# CM4_Conn.net
KiCad netlist of a schematic drawn in Altium Designer
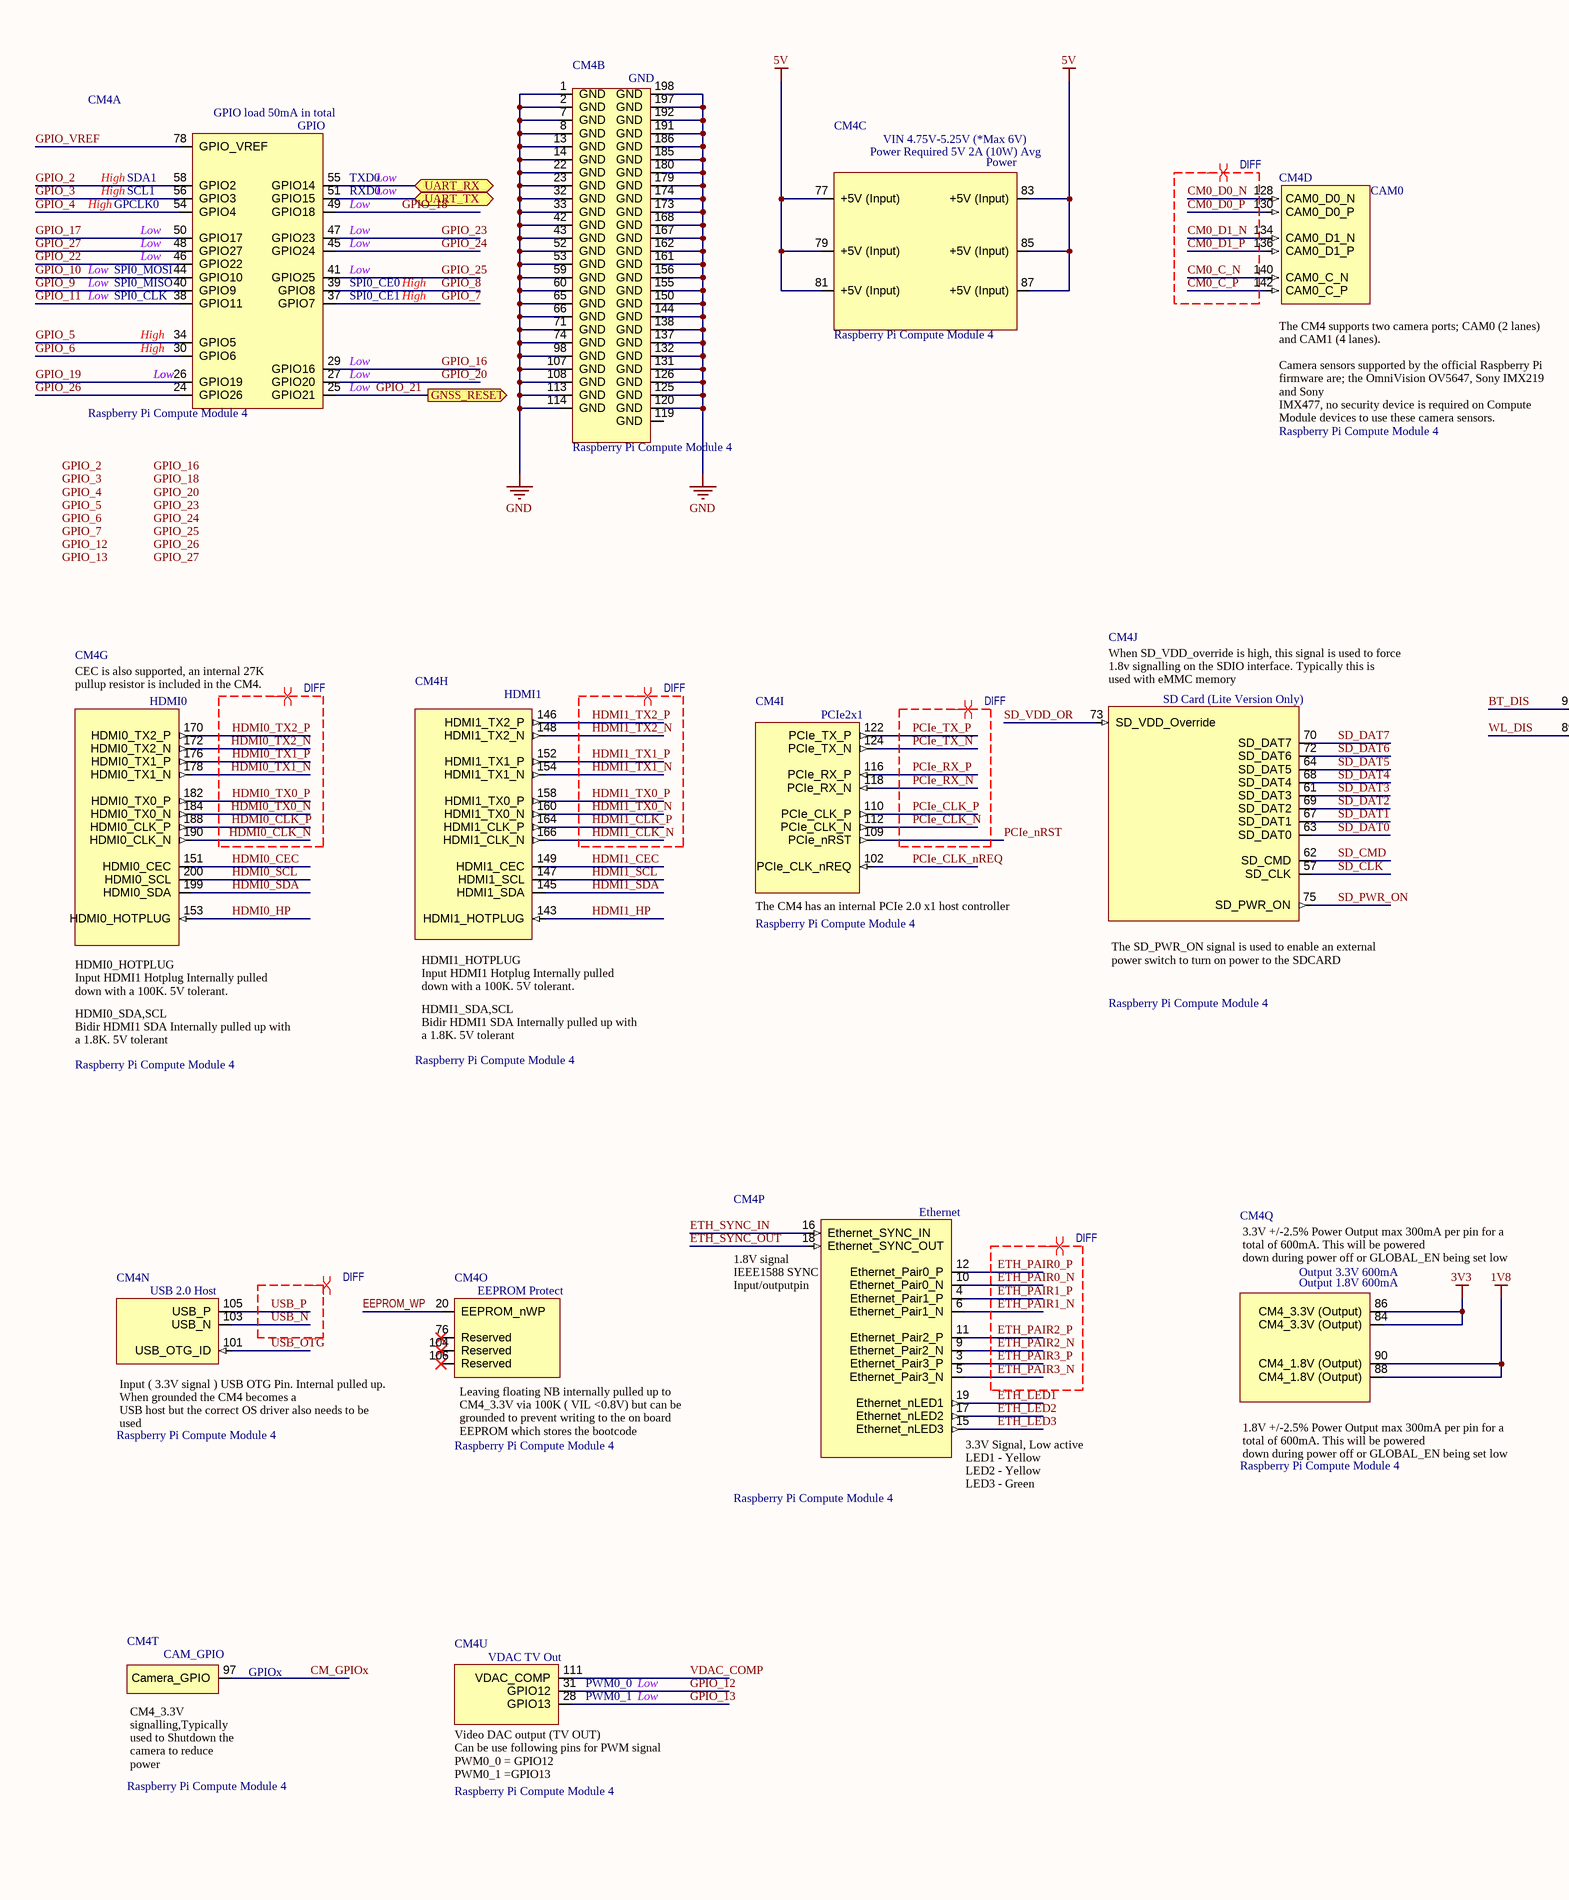
[diagram p0: CM4_Conn.SchDoc, left]
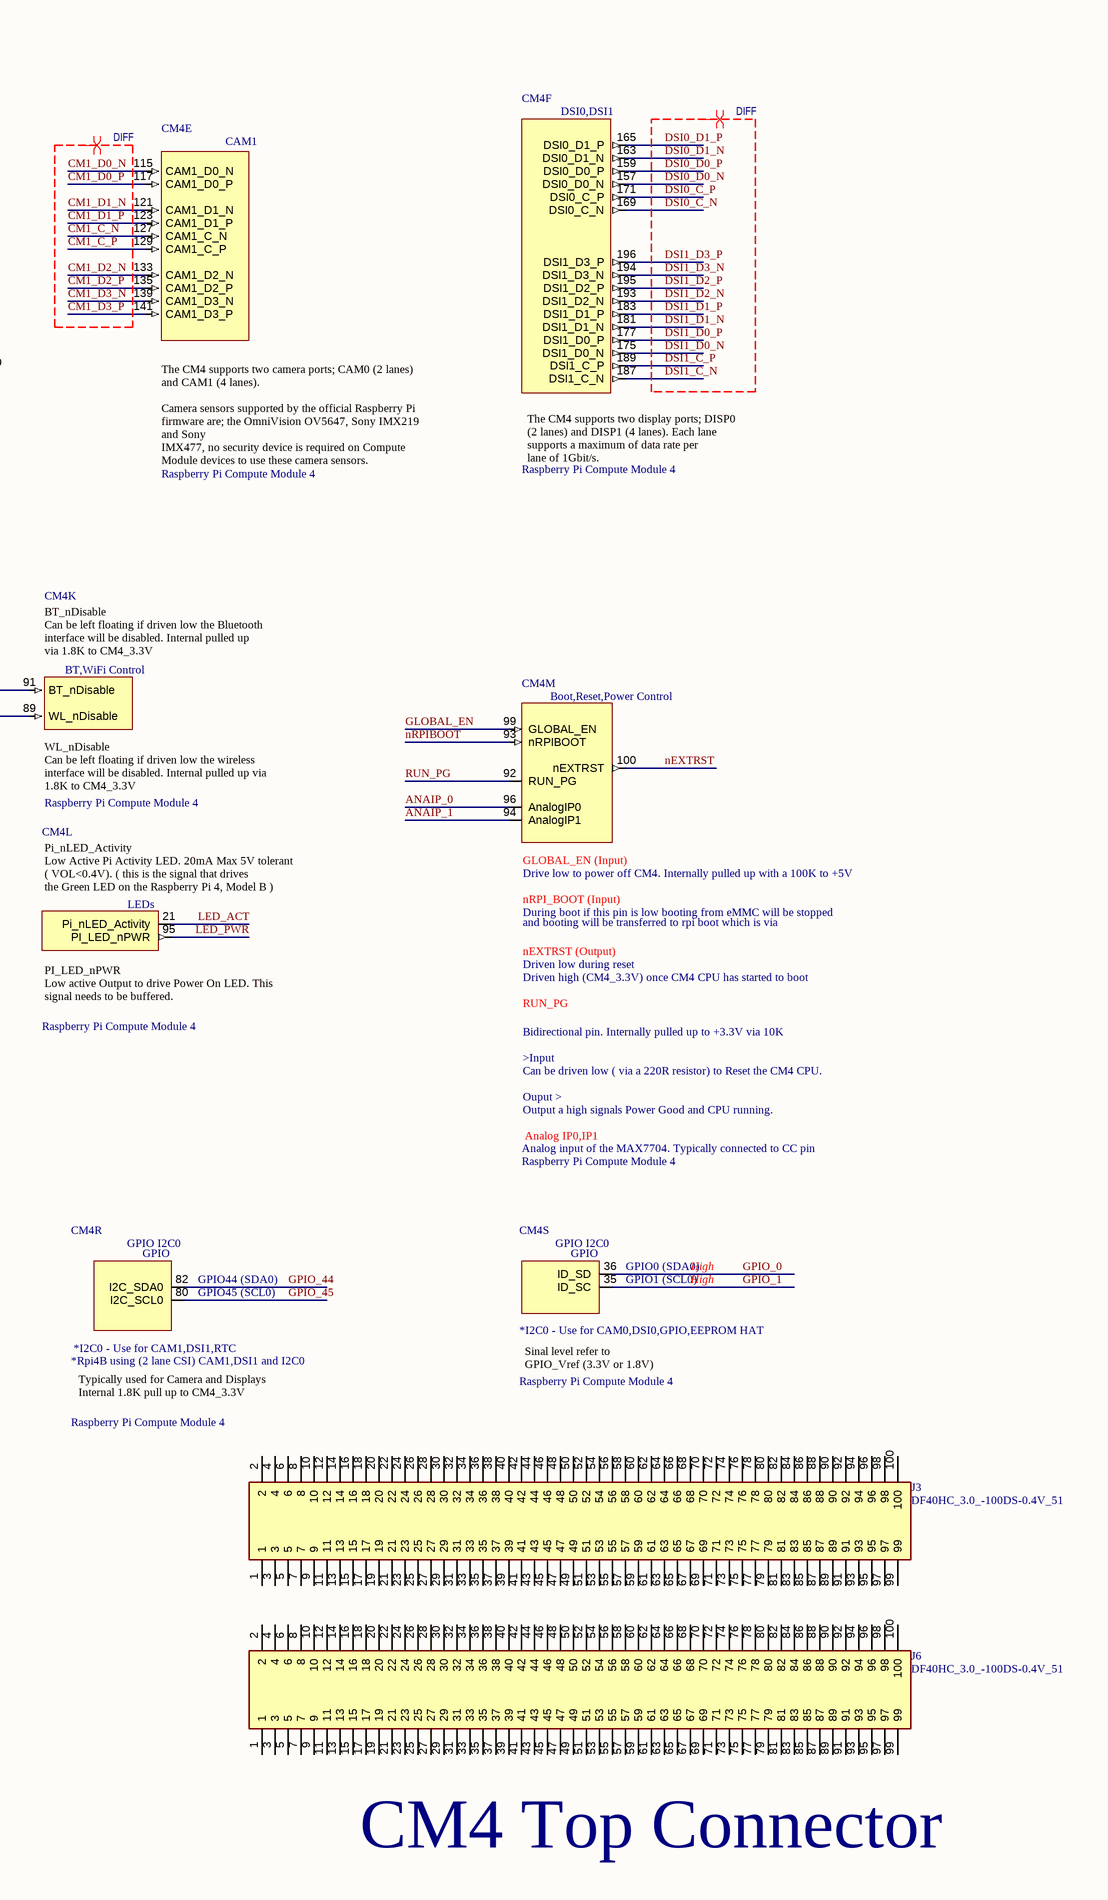
[diagram p1: CM4_Conn.SchDoc, right]

(export (version "E")
  (design (tool "Eeschema 10.0.6"))
  (components
    (comp (ref "CM4")
      (value "Raspberry Pi Compute Module 4")
      (footprint "CM4-F40C-100DS-0.4v_1.5mm_0mm")
      (description "Raspberry Pi Compute Module 4 by Amornthep Phunsin")
      (libsource (lib "CM4") (part "CM4"))
    )
    (comp (ref "J3")
      (value "DF40HC_3.0_-100DS-0.4V_51")
      (footprint "SamacSys:DF40HC30100DS04V51")
      (description "Connector")
      (fields
        (field (name "MANUFACTURER_PART_NUMBER") "DF40HC(3.0)-100DS-0.4V(51")
        (field (name "MOUSER PART NUMBER") "798-DF40HC30100DS451")
      )
      (libsource (lib "SamacSys") (part "DF40HC_3.0_-100DS-0.4V_51"))
    )
    (comp (ref "J6")
      (value "DF40HC_3.0_-100DS-0.4V_51")
      (footprint "SamacSys:DF40HC30100DS04V51")
      (description "Connector")
      (fields
        (field (name "MANUFACTURER_PART_NUMBER") "DF40HC(3.0)-100DS-0.4V(51")
        (field (name "MOUSER PART NUMBER") "798-DF40HC30100DS451")
      )
      (libsource (lib "SamacSys") (part "DF40HC_3.0_-100DS-0.4V_51"))
    )
  )
  (nets
    (net (code "1") (name "/ANAIP_0") (class "Default")
      (node (ref "CM4") (pin "96") (pinfunction "AnalogIP0_96") (pintype "passive"))
    )
    (net (code "2") (name "/ANAIP_1") (class "Default")
      (node (ref "CM4") (pin "94") (pinfunction "AnalogIP1_94") (pintype "passive"))
    )
    (net (code "3") (name "/BT_DIS") (class "Default")
      (node (ref "CM4") (pin "91") (pinfunction "BT_nDisable_91") (pintype "input"))
    )
    (net (code "4") (name "/CM0_C_N") (class "Default")
      (node (ref "CM4") (pin "140") (pinfunction "CAM0_C_N_140") (pintype "input"))
    )
    (net (code "5") (name "/CM0_C_P") (class "Default")
      (node (ref "CM4") (pin "142") (pinfunction "CAM0_C_P_142") (pintype "input"))
    )
    (net (code "6") (name "/CM0_D0_N") (class "Default")
      (node (ref "CM4") (pin "128") (pinfunction "CAM0_D0_N_128") (pintype "input"))
    )
    (net (code "7") (name "/CM0_D0_P") (class "Default")
      (node (ref "CM4") (pin "130") (pinfunction "CAM0_D0_P_130") (pintype "input"))
    )
    (net (code "8") (name "/CM0_D1_N") (class "Default")
      (node (ref "CM4") (pin "134") (pinfunction "CAM0_D1_N_134") (pintype "input"))
    )
    (net (code "9") (name "/CM0_D1_P") (class "Default")
      (node (ref "CM4") (pin "136") (pinfunction "CAM0_D1_P_136") (pintype "input"))
    )
    (net (code "10") (name "/CM1_C_N") (class "Default")
      (node (ref "CM4") (pin "127") (pinfunction "CAM1_C_N_127") (pintype "input"))
    )
    (net (code "11") (name "/CM1_C_P") (class "Default")
      (node (ref "CM4") (pin "129") (pinfunction "CAM1_C_P_129") (pintype "input"))
    )
    (net (code "12") (name "/CM1_D0_N") (class "Default")
      (node (ref "CM4") (pin "115") (pinfunction "CAM1_D0_N_115") (pintype "input"))
    )
    (net (code "13") (name "/CM1_D0_P") (class "Default")
      (node (ref "CM4") (pin "117") (pinfunction "CAM1_D0_P_117") (pintype "input"))
    )
    (net (code "14") (name "/CM1_D1_N") (class "Default")
      (node (ref "CM4") (pin "121") (pinfunction "CAM1_D1_N_121") (pintype "input"))
    )
    (net (code "15") (name "/CM1_D1_P") (class "Default")
      (node (ref "CM4") (pin "123") (pinfunction "CAM1_D1_P_123") (pintype "input"))
    )
    (net (code "16") (name "/CM1_D2_N") (class "Default")
      (node (ref "CM4") (pin "133") (pinfunction "CAM1_D2_N_133") (pintype "input"))
    )
    (net (code "17") (name "/CM1_D2_P") (class "Default")
      (node (ref "CM4") (pin "135") (pinfunction "CAM1_D2_P_135") (pintype "input"))
    )
    (net (code "18") (name "/CM1_D3_N") (class "Default")
      (node (ref "CM4") (pin "139") (pinfunction "CAM1_D3_N_139") (pintype "input"))
    )
    (net (code "19") (name "/CM1_D3_P") (class "Default")
      (node (ref "CM4") (pin "141") (pinfunction "CAM1_D3_P_141") (pintype "input"))
    )
    (net (code "20") (name "/CM_GPIOx") (class "Default")
      (node (ref "CM4") (pin "97") (pinfunction "Camera_GPIO_97") (pintype "passive"))
    )
    (net (code "21") (name "/DSI0_C_N") (class "Default")
      (node (ref "CM4") (pin "169") (pinfunction "DSI0_C_N_169") (pintype "output"))
    )
    (net (code "22") (name "/DSI0_C_P") (class "Default")
      (node (ref "CM4") (pin "171") (pinfunction "DSI0_C_P_171") (pintype "output"))
    )
    (net (code "23") (name "/DSI0_D0_N") (class "Default")
      (node (ref "CM4") (pin "157") (pinfunction "DSI0_D0_N_157") (pintype "output"))
    )
    (net (code "24") (name "/DSI0_D0_P") (class "Default")
      (node (ref "CM4") (pin "159") (pinfunction "DSI0_D0_P_159") (pintype "output"))
    )
    (net (code "25") (name "/DSI0_D1_N") (class "Default")
      (node (ref "CM4") (pin "163") (pinfunction "DSI0_D1_N_163") (pintype "output"))
    )
    (net (code "26") (name "/DSI0_D1_P") (class "Default")
      (node (ref "CM4") (pin "165") (pinfunction "DSI0_D1_P_165") (pintype "output"))
    )
    (net (code "27") (name "/DSI1_C_N") (class "Default")
      (node (ref "CM4") (pin "187") (pinfunction "DSI1_C_N_187") (pintype "output"))
    )
    (net (code "28") (name "/DSI1_C_P") (class "Default")
      (node (ref "CM4") (pin "189") (pinfunction "DSI1_C_P_189") (pintype "output"))
    )
    (net (code "29") (name "/DSI1_D0_N") (class "Default")
      (node (ref "CM4") (pin "175") (pinfunction "DSI1_D0_N_175") (pintype "output"))
    )
    (net (code "30") (name "/DSI1_D0_P") (class "Default")
      (node (ref "CM4") (pin "177") (pinfunction "DSI1_D0_P_177") (pintype "output"))
    )
    (net (code "31") (name "/DSI1_D1_N") (class "Default")
      (node (ref "CM4") (pin "181") (pinfunction "DSI1_D1_N_181") (pintype "output"))
    )
    (net (code "32") (name "/DSI1_D1_P") (class "Default")
      (node (ref "CM4") (pin "183") (pinfunction "DSI1_D1_P_183") (pintype "output"))
    )
    (net (code "33") (name "/DSI1_D2_N") (class "Default")
      (node (ref "CM4") (pin "193") (pinfunction "DSI1_D2_N_193") (pintype "output"))
    )
    (net (code "34") (name "/DSI1_D2_P") (class "Default")
      (node (ref "CM4") (pin "195") (pinfunction "DSI1_D2_P_195") (pintype "output"))
    )
    (net (code "35") (name "/DSI1_D3_N") (class "Default")
      (node (ref "CM4") (pin "194") (pinfunction "DSI1_D3_N_194") (pintype "output"))
    )
    (net (code "36") (name "/DSI1_D3_P") (class "Default")
      (node (ref "CM4") (pin "196") (pinfunction "DSI1_D3_P_196") (pintype "output"))
    )
    (net (code "37") (name "/EEPROM_WP") (class "Default")
      (node (ref "CM4") (pin "20") (pinfunction "EEPROM_nWP_20") (pintype "passive"))
    )
    (net (code "38") (name "/ETH_LED1") (class "Default")
      (node (ref "CM4") (pin "19") (pinfunction "Ethernet_nLED1_19") (pintype "output"))
    )
    (net (code "39") (name "/ETH_LED2") (class "Default")
      (node (ref "CM4") (pin "17") (pinfunction "Ethernet_nLED2_17") (pintype "output"))
    )
    (net (code "40") (name "/ETH_LED3") (class "Default")
      (node (ref "CM4") (pin "15") (pinfunction "Ethernet_nLED3_15") (pintype "output"))
    )
    (net (code "41") (name "/ETH_PAIR0_N") (class "Default")
      (node (ref "CM4") (pin "10") (pinfunction "Ethernet_Pair0_N_10") (pintype "passive"))
    )
    (net (code "42") (name "/ETH_PAIR0_P") (class "Default")
      (node (ref "CM4") (pin "12") (pinfunction "Ethernet_Pair0_P_12") (pintype "passive"))
    )
    (net (code "43") (name "/ETH_PAIR1_N") (class "Default")
      (node (ref "CM4") (pin "6") (pinfunction "Ethernet_Pair1_N_6") (pintype "passive"))
    )
    (net (code "44") (name "/ETH_PAIR1_P") (class "Default")
      (node (ref "CM4") (pin "4") (pinfunction "Ethernet_Pair1_P_4") (pintype "passive"))
    )
    (net (code "45") (name "/ETH_PAIR2_N") (class "Default")
      (node (ref "CM4") (pin "9") (pinfunction "Ethernet_Pair2_N_9") (pintype "passive"))
    )
    (net (code "46") (name "/ETH_PAIR2_P") (class "Default")
      (node (ref "CM4") (pin "11") (pinfunction "Ethernet_Pair2_P_11") (pintype "passive"))
    )
    (net (code "47") (name "/ETH_PAIR3_N") (class "Default")
      (node (ref "CM4") (pin "5") (pinfunction "Ethernet_Pair3_N_5") (pintype "passive"))
    )
    (net (code "48") (name "/ETH_PAIR3_P") (class "Default")
      (node (ref "CM4") (pin "3") (pinfunction "Ethernet_Pair3_P_3") (pintype "passive"))
    )
    (net (code "49") (name "/ETH_SYNC_IN") (class "Default")
      (node (ref "CM4") (pin "16") (pinfunction "Ethernet_SYNC_IN_16") (pintype "input"))
    )
    (net (code "50") (name "/ETH_SYNC_OUT") (class "Default")
      (node (ref "CM4") (pin "18") (pinfunction "Ethernet_SYNC_OUT_18") (pintype "input"))
    )
    (net (code "51") (name "/GLOBAL_EN") (class "Default")
      (node (ref "CM4") (pin "99") (pinfunction "GLOBAL_EN_99") (pintype "input"))
    )
    (net (code "52") (name "/GPIO_0") (class "Default")
      (node (ref "CM4") (pin "36") (pinfunction "ID_SD_36") (pintype "passive"))
    )
    (net (code "53") (name "/GPIO_1") (class "Default")
      (node (ref "CM4") (pin "35") (pinfunction "ID_SC_35") (pintype "passive"))
    )
    (net (code "54") (name "/GPIO_2") (class "Default")
      (node (ref "CM4") (pin "58") (pinfunction "GPIO2_58") (pintype "passive"))
    )
    (net (code "55") (name "/GPIO_3") (class "Default")
      (node (ref "CM4") (pin "56") (pinfunction "GPIO3_56") (pintype "passive"))
    )
    (net (code "56") (name "/GPIO_4") (class "Default")
      (node (ref "CM4") (pin "54") (pinfunction "GPIO4_54") (pintype "passive"))
    )
    (net (code "57") (name "/GPIO_5") (class "Default")
      (node (ref "CM4") (pin "34") (pinfunction "GPIO5_34") (pintype "passive"))
    )
    (net (code "58") (name "/GPIO_6") (class "Default")
      (node (ref "CM4") (pin "30") (pinfunction "GPIO6_30") (pintype "passive"))
    )
    (net (code "59") (name "/GPIO_7") (class "Default")
      (node (ref "CM4") (pin "37") (pinfunction "GPIO7_37") (pintype "passive"))
    )
    (net (code "60") (name "/GPIO_8") (class "Default")
      (node (ref "CM4") (pin "39") (pinfunction "GPIO8_39") (pintype "passive"))
    )
    (net (code "61") (name "/GPIO_9") (class "Default")
      (node (ref "CM4") (pin "40") (pinfunction "GPIO9_40") (pintype "passive"))
    )
    (net (code "62") (name "/GPIO_10") (class "Default")
      (node (ref "CM4") (pin "44") (pinfunction "GPIO10_44") (pintype "passive"))
    )
    (net (code "63") (name "/GPIO_11") (class "Default")
      (node (ref "CM4") (pin "38") (pinfunction "GPIO11_38") (pintype "passive"))
    )
    (net (code "64") (name "/GPIO_12") (class "Default")
      (node (ref "CM4") (pin "31") (pinfunction "GPIO12_31") (pintype "passive"))
    )
    (net (code "65") (name "/GPIO_13") (class "Default")
      (node (ref "CM4") (pin "28") (pinfunction "GPIO13_28") (pintype "passive"))
    )
    (net (code "66") (name "/GPIO_16") (class "Default")
      (node (ref "CM4") (pin "29") (pinfunction "GPIO16_29") (pintype "passive"))
    )
    (net (code "67") (name "/GPIO_17") (class "Default")
      (node (ref "CM4") (pin "50") (pinfunction "GPIO17_50") (pintype "passive"))
    )
    (net (code "68") (name "/GPIO_18") (class "Default")
      (node (ref "CM4") (pin "49") (pinfunction "GPIO18_49") (pintype "passive"))
    )
    (net (code "69") (name "/GPIO_19") (class "Default")
      (node (ref "CM4") (pin "26") (pinfunction "GPIO19_26") (pintype "passive"))
    )
    (net (code "70") (name "/GPIO_20") (class "Default")
      (node (ref "CM4") (pin "27") (pinfunction "GPIO20_27") (pintype "passive"))
    )
    (net (code "71") (name "/GPIO_21") (class "Default")
      (node (ref "CM4") (pin "25") (pinfunction "GPIO21_25") (pintype "passive"))
    )
    (net (code "72") (name "/GPIO_22") (class "Default")
      (node (ref "CM4") (pin "46") (pinfunction "GPIO22_46") (pintype "passive"))
    )
    (net (code "73") (name "/GPIO_23") (class "Default")
      (node (ref "CM4") (pin "47") (pinfunction "GPIO23_47") (pintype "passive"))
    )
    (net (code "74") (name "/GPIO_24") (class "Default")
      (node (ref "CM4") (pin "45") (pinfunction "GPIO24_45") (pintype "passive"))
    )
    (net (code "75") (name "/GPIO_25") (class "Default")
      (node (ref "CM4") (pin "41") (pinfunction "GPIO25_41") (pintype "passive"))
    )
    (net (code "76") (name "/GPIO_26") (class "Default")
      (node (ref "CM4") (pin "24") (pinfunction "GPIO26_24") (pintype "passive"))
    )
    (net (code "77") (name "/GPIO_27") (class "Default")
      (node (ref "CM4") (pin "48") (pinfunction "GPIO27_48") (pintype "passive"))
    )
    (net (code "78") (name "/GPIO_44") (class "Default")
      (node (ref "CM4") (pin "82") (pinfunction "I2C_SDA0_82") (pintype "passive"))
    )
    (net (code "79") (name "/GPIO_45") (class "Default")
      (node (ref "CM4") (pin "80") (pinfunction "I2C_SCL0_80") (pintype "passive"))
    )
    (net (code "80") (name "/GPIO_VREF") (class "Default")
      (node (ref "CM4") (pin "78") (pinfunction "GPIO_VREF_78") (pintype "power_in"))
    )
    (net (code "81") (name "/HDMI0_CEC") (class "Default")
      (node (ref "CM4") (pin "151") (pinfunction "HDMI0_CEC_151") (pintype "open_collector"))
    )
    (net (code "82") (name "/HDMI0_CLK_N") (class "Default")
      (node (ref "CM4") (pin "190") (pinfunction "HDMI0_CLK_N_190") (pintype "output"))
    )
    (net (code "83") (name "/HDMI0_CLK_P") (class "Default")
      (node (ref "CM4") (pin "188") (pinfunction "HDMI0_CLK_P_188") (pintype "output"))
    )
    (net (code "84") (name "/HDMI0_HP") (class "Default")
      (node (ref "CM4") (pin "153") (pinfunction "HDMI0_HOTPLUG_153") (pintype "input"))
    )
    (net (code "85") (name "/HDMI0_SCL") (class "Default")
      (node (ref "CM4") (pin "200") (pinfunction "HDMI0_SCL_200") (pintype "open_collector"))
    )
    (net (code "86") (name "/HDMI0_SDA") (class "Default")
      (node (ref "CM4") (pin "199") (pinfunction "HDMI0_SDA_199") (pintype "bidirectional"))
    )
    (net (code "87") (name "/HDMI0_TX0_N") (class "Default")
      (node (ref "CM4") (pin "184") (pinfunction "HDMI0_TX0_N_184") (pintype "output"))
    )
    (net (code "88") (name "/HDMI0_TX0_P") (class "Default")
      (node (ref "CM4") (pin "182") (pinfunction "HDMI0_TX0_P_182") (pintype "output"))
    )
    (net (code "89") (name "/HDMI0_TX1_N") (class "Default")
      (node (ref "CM4") (pin "178") (pinfunction "HDMI0_TX1_N_178") (pintype "output"))
    )
    (net (code "90") (name "/HDMI0_TX1_P") (class "Default")
      (node (ref "CM4") (pin "176") (pinfunction "HDMI0_TX1_P_176") (pintype "output"))
    )
    (net (code "91") (name "/HDMI0_TX2_N") (class "Default")
      (node (ref "CM4") (pin "172") (pinfunction "HDMI0_TX2_N_172") (pintype "output"))
    )
    (net (code "92") (name "/HDMI0_TX2_P") (class "Default")
      (node (ref "CM4") (pin "170") (pinfunction "HDMI0_TX2_P_170") (pintype "output"))
    )
    (net (code "93") (name "/HDMI1_CEC") (class "Default")
      (node (ref "CM4") (pin "149") (pinfunction "HDMI1_CEC_149") (pintype "open_collector"))
    )
    (net (code "94") (name "/HDMI1_CLK_N") (class "Default")
      (node (ref "CM4") (pin "166") (pinfunction "HDMI1_CLK_N_166") (pintype "output"))
    )
    (net (code "95") (name "/HDMI1_CLK_P") (class "Default")
      (node (ref "CM4") (pin "164") (pinfunction "HDMI1_CLK_P_164") (pintype "output"))
    )
    (net (code "96") (name "/HDMI1_HP") (class "Default")
      (node (ref "CM4") (pin "143") (pinfunction "HDMI1_HOTPLUG_143") (pintype "input"))
    )
    (net (code "97") (name "/HDMI1_SCL") (class "Default")
      (node (ref "CM4") (pin "147") (pinfunction "HDMI1_SCL_147") (pintype "open_collector"))
    )
    (net (code "98") (name "/HDMI1_SDA") (class "Default")
      (node (ref "CM4") (pin "145") (pinfunction "HDMI1_SDA_145") (pintype "bidirectional"))
    )
    (net (code "99") (name "/HDMI1_TX0_N") (class "Default")
      (node (ref "CM4") (pin "160") (pinfunction "HDMI1_TX0_N_160") (pintype "output"))
    )
    (net (code "100") (name "/HDMI1_TX0_P") (class "Default")
      (node (ref "CM4") (pin "158") (pinfunction "HDMI1_TX0_P_158") (pintype "output"))
    )
    (net (code "101") (name "/HDMI1_TX1_N") (class "Default")
      (node (ref "CM4") (pin "154") (pinfunction "HDMI1_TX1_N_154") (pintype "output"))
    )
    (net (code "102") (name "/HDMI1_TX1_P") (class "Default")
      (node (ref "CM4") (pin "152") (pinfunction "HDMI1_TX1_P_152") (pintype "output"))
    )
    (net (code "103") (name "/HDMI1_TX2_N") (class "Default")
      (node (ref "CM4") (pin "148") (pinfunction "HDMI1_TX2_N_148") (pintype "output"))
    )
    (net (code "104") (name "/HDMI1_TX2_P") (class "Default")
      (node (ref "CM4") (pin "146") (pinfunction "HDMI1_TX2_P_146") (pintype "output"))
    )
    (net (code "105") (name "/LED_ACT") (class "Default")
      (node (ref "CM4") (pin "21") (pinfunction "Pi_nLED_Activity_21") (pintype "open_collector"))
    )
    (net (code "106") (name "/LED_PWR") (class "Default")
      (node (ref "CM4") (pin "95") (pinfunction "PI_LED_nPWR_95") (pintype "output"))
    )
    (net (code "107") (name "/PCIe_CLK_N") (class "Default")
      (node (ref "CM4") (pin "112") (pinfunction "PCIe_CLK_N_112") (pintype "output"))
    )
    (net (code "108") (name "/PCIe_CLK_P") (class "Default")
      (node (ref "CM4") (pin "110") (pinfunction "PCIe_CLK_P_110") (pintype "output"))
    )
    (net (code "109") (name "/PCIe_CLK_nREQ") (class "Default")
      (node (ref "CM4") (pin "102") (pinfunction "PCIe_CLK_nREQ_102") (pintype "input"))
    )
    (net (code "110") (name "/PCIe_RX_N") (class "Default")
      (node (ref "CM4") (pin "118") (pinfunction "PCIe_RX_N_118") (pintype "input"))
    )
    (net (code "111") (name "/PCIe_RX_P") (class "Default")
      (node (ref "CM4") (pin "116") (pinfunction "PCIe_RX_P_116") (pintype "input"))
    )
    (net (code "112") (name "/PCIe_TX_N") (class "Default")
      (node (ref "CM4") (pin "124") (pinfunction "PCIe_TX_N_124") (pintype "output"))
    )
    (net (code "113") (name "/PCIe_TX_P") (class "Default")
      (node (ref "CM4") (pin "122") (pinfunction "PCIe_TX_P_122") (pintype "output"))
    )
    (net (code "114") (name "/PCIe_nRST") (class "Default")
      (node (ref "CM4") (pin "109") (pinfunction "PCIe_nRST_109") (pintype "output"))
    )
    (net (code "115") (name "/RUN_PG") (class "Default")
      (node (ref "CM4") (pin "92") (pinfunction "RUN_PG_92") (pintype "passive"))
    )
    (net (code "116") (name "/SD_CLK") (class "Default")
      (node (ref "CM4") (pin "57") (pinfunction "SD_CLK_57") (pintype "passive"))
    )
    (net (code "117") (name "/SD_CMD") (class "Default")
      (node (ref "CM4") (pin "62") (pinfunction "SD_CMD_62") (pintype "passive"))
    )
    (net (code "118") (name "/SD_DAT0") (class "Default")
      (node (ref "CM4") (pin "63") (pinfunction "SD_DAT0_63") (pintype "passive"))
    )
    (net (code "119") (name "/SD_DAT1") (class "Default")
      (node (ref "CM4") (pin "67") (pinfunction "SD_DAT1_67") (pintype "passive"))
    )
    (net (code "120") (name "/SD_DAT2") (class "Default")
      (node (ref "CM4") (pin "69") (pinfunction "SD_DAT2_69") (pintype "passive"))
    )
    (net (code "121") (name "/SD_DAT3") (class "Default")
      (node (ref "CM4") (pin "61") (pinfunction "SD_DAT3_61") (pintype "passive"))
    )
    (net (code "122") (name "/SD_DAT4") (class "Default")
      (node (ref "CM4") (pin "68") (pinfunction "SD_DAT4_68") (pintype "passive"))
    )
    (net (code "123") (name "/SD_DAT5") (class "Default")
      (node (ref "CM4") (pin "64") (pinfunction "SD_DAT5_64") (pintype "passive"))
    )
    (net (code "124") (name "/SD_DAT6") (class "Default")
      (node (ref "CM4") (pin "72") (pinfunction "SD_DAT6_72") (pintype "passive"))
    )
    (net (code "125") (name "/SD_DAT7") (class "Default")
      (node (ref "CM4") (pin "70") (pinfunction "SD_DAT7_70") (pintype "passive"))
    )
    (net (code "126") (name "/SD_PWR_ON") (class "Default")
      (node (ref "CM4") (pin "75") (pinfunction "SD_PWR_ON_75") (pintype "output"))
    )
    (net (code "127") (name "/SD_VDD_OR") (class "Default")
      (node (ref "CM4") (pin "73") (pinfunction "SD_VDD_Override_73") (pintype "input"))
    )
    (net (code "128") (name "/UART_RX") (class "Default")
      (node (ref "CM4") (pin "55") (pinfunction "GPIO14_55") (pintype "passive"))
    )
    (net (code "129") (name "/UART_TX") (class "Default")
      (node (ref "CM4") (pin "51") (pinfunction "GPIO15_51") (pintype "passive"))
    )
    (net (code "130") (name "/USB_N") (class "Default")
      (node (ref "CM4") (pin "103") (pinfunction "USB_N_103") (pintype "passive"))
    )
    (net (code "131") (name "/USB_OTG") (class "Default")
      (node (ref "CM4") (pin "101") (pinfunction "USB_OTG_ID_101") (pintype "input"))
    )
    (net (code "132") (name "/USB_P") (class "Default")
      (node (ref "CM4") (pin "105") (pinfunction "USB_P_105") (pintype "passive"))
    )
    (net (code "133") (name "/VDAC_COMP") (class "Default")
      (node (ref "CM4") (pin "111") (pinfunction "VDAC_COMP_111") (pintype "passive"))
    )
    (net (code "134") (name "/WL_DIS") (class "Default")
      (node (ref "CM4") (pin "89") (pinfunction "WL_nDisable_89") (pintype "input"))
    )
    (net (code "135") (name "/nEXTRST") (class "Default")
      (node (ref "CM4") (pin "100") (pinfunction "nEXTRST_100") (pintype "output"))
    )
    (net (code "136") (name "/nRPIBOOT") (class "Default")
      (node (ref "CM4") (pin "93") (pinfunction "nRPIBOOT_93") (pintype "input"))
    )
    (net (code "137") (name "1V8") (class "Default")
      (node (ref "CM4") (pin "88") (pinfunction "CM4_1.8V_(Output)_88") (pintype "power_in"))
      (node (ref "CM4") (pin "90") (pinfunction "CM4_1.8V_(Output)_90") (pintype "power_in"))
    )
    (net (code "138") (name "3V3") (class "Default")
      (node (ref "CM4") (pin "84") (pinfunction "CM4_3.3V_(Output)_84") (pintype "power_in"))
      (node (ref "CM4") (pin "86") (pinfunction "CM4_3.3V_(Output)_86") (pintype "power_in"))
    )
    (net (code "139") (name "5V") (class "Default")
      (node (ref "CM4") (pin "77") (pinfunction "+5V_(Input)_77") (pintype "power_in"))
      (node (ref "CM4") (pin "79") (pinfunction "+5V_(Input)_79") (pintype "power_in"))
      (node (ref "CM4") (pin "81") (pinfunction "+5V_(Input)_81") (pintype "power_in"))
      (node (ref "CM4") (pin "83") (pinfunction "+5V_(Input)_83") (pintype "power_in"))
      (node (ref "CM4") (pin "85") (pinfunction "+5V_(Input)_85") (pintype "power_in"))
      (node (ref "CM4") (pin "87") (pinfunction "+5V_(Input)_87") (pintype "power_in"))
    )
    (net (code "140") (name "GND") (class "Default")
      (node (ref "CM4") (pin "1") (pinfunction "GND_1") (pintype "power_in"))
      (node (ref "CM4") (pin "107") (pinfunction "GND_107") (pintype "power_in"))
      (node (ref "CM4") (pin "108") (pinfunction "GND_108") (pintype "power_in"))
      (node (ref "CM4") (pin "113") (pinfunction "GND_113") (pintype "power_in"))
      (node (ref "CM4") (pin "114") (pinfunction "GND_114") (pintype "power_in"))
      (node (ref "CM4") (pin "120") (pinfunction "GND_120") (pintype "power_in"))
      (node (ref "CM4") (pin "125") (pinfunction "GND_125") (pintype "power_in"))
      (node (ref "CM4") (pin "126") (pinfunction "GND_126") (pintype "power_in"))
      (node (ref "CM4") (pin "13") (pinfunction "GND_13") (pintype "power_in"))
      (node (ref "CM4") (pin "131") (pinfunction "GND_131") (pintype "power_in"))
      (node (ref "CM4") (pin "132") (pinfunction "GND_132") (pintype "power_in"))
      (node (ref "CM4") (pin "137") (pinfunction "GND_137") (pintype "power_in"))
      (node (ref "CM4") (pin "138") (pinfunction "GND_138") (pintype "power_in"))
      (node (ref "CM4") (pin "14") (pinfunction "GND_14") (pintype "power_in"))
      (node (ref "CM4") (pin "144") (pinfunction "GND_144") (pintype "power_in"))
      (node (ref "CM4") (pin "150") (pinfunction "GND_150") (pintype "power_in"))
      (node (ref "CM4") (pin "155") (pinfunction "GND_155") (pintype "power_in"))
      (node (ref "CM4") (pin "156") (pinfunction "GND_156") (pintype "power_in"))
      (node (ref "CM4") (pin "161") (pinfunction "GND_161") (pintype "power_in"))
      (node (ref "CM4") (pin "162") (pinfunction "GND_162") (pintype "power_in"))
      (node (ref "CM4") (pin "167") (pinfunction "GND_167") (pintype "power_in"))
      (node (ref "CM4") (pin "168") (pinfunction "GND_168") (pintype "power_in"))
      (node (ref "CM4") (pin "173") (pinfunction "GND_173") (pintype "power_in"))
      (node (ref "CM4") (pin "174") (pinfunction "GND_174") (pintype "power_in"))
      (node (ref "CM4") (pin "179") (pinfunction "GND_179") (pintype "power_in"))
      (node (ref "CM4") (pin "180") (pinfunction "GND_180") (pintype "power_in"))
      (node (ref "CM4") (pin "185") (pinfunction "GND_185") (pintype "power_in"))
      (node (ref "CM4") (pin "186") (pinfunction "GND_186") (pintype "power_in"))
      (node (ref "CM4") (pin "191") (pinfunction "GND_191") (pintype "power_in"))
      (node (ref "CM4") (pin "192") (pinfunction "GND_192") (pintype "power_in"))
      (node (ref "CM4") (pin "197") (pinfunction "GND_197") (pintype "power_in"))
      (node (ref "CM4") (pin "198") (pinfunction "GND_198") (pintype "power_in"))
      (node (ref "CM4") (pin "2") (pinfunction "GND_2") (pintype "power_in"))
      (node (ref "CM4") (pin "22") (pinfunction "GND_22") (pintype "power_in"))
      (node (ref "CM4") (pin "23") (pinfunction "GND_23") (pintype "power_in"))
      (node (ref "CM4") (pin "32") (pinfunction "GND_32") (pintype "power_in"))
      (node (ref "CM4") (pin "33") (pinfunction "GND_33") (pintype "power_in"))
      (node (ref "CM4") (pin "42") (pinfunction "GND_42") (pintype "power_in"))
      (node (ref "CM4") (pin "43") (pinfunction "GND_43") (pintype "power_in"))
      (node (ref "CM4") (pin "52") (pinfunction "GND_52") (pintype "power_in"))
      (node (ref "CM4") (pin "53") (pinfunction "GND_53") (pintype "power_in"))
      (node (ref "CM4") (pin "59") (pinfunction "GND_59") (pintype "power_in"))
      (node (ref "CM4") (pin "60") (pinfunction "GND_60") (pintype "power_in"))
      (node (ref "CM4") (pin "65") (pinfunction "GND_65") (pintype "power_in"))
      (node (ref "CM4") (pin "66") (pinfunction "GND_66") (pintype "power_in"))
      (node (ref "CM4") (pin "7") (pinfunction "GND_7") (pintype "power_in"))
      (node (ref "CM4") (pin "71") (pinfunction "GND_71") (pintype "power_in"))
      (node (ref "CM4") (pin "74") (pinfunction "GND_74") (pintype "power_in"))
      (node (ref "CM4") (pin "8") (pinfunction "GND_8") (pintype "power_in"))
      (node (ref "CM4") (pin "98") (pinfunction "GND_98") (pintype "power_in"))
    )
    (net (code "141") (name "unconnected-(CM4B-GND-Pad119)") (class "Default")
      (node (ref "CM4") (pin "119") (pinfunction "GND_119") (pintype "power_in"))
    )
    (net (code "142") (name "unconnected-(CM4O-Reserved-Pad76)") (class "Default")
      (node (ref "CM4") (pin "76") (pinfunction "Reserved_76") (pintype "passive+no_connect"))
    )
    (net (code "143") (name "unconnected-(CM4O-Reserved-Pad104)") (class "Default")
      (node (ref "CM4") (pin "104") (pinfunction "Reserved_104") (pintype "passive+no_connect"))
    )
    (net (code "144") (name "unconnected-(CM4O-Reserved-Pad106)") (class "Default")
      (node (ref "CM4") (pin "106") (pinfunction "Reserved_106") (pintype "passive+no_connect"))
    )
    (net (code "145") (name "unconnected-(J3-Pad1)") (class "Default")
      (node (ref "J3") (pin "1") (pinfunction "1_1") (pintype "passive"))
    )
    (net (code "146") (name "unconnected-(J3-Pad2)") (class "Default")
      (node (ref "J3") (pin "2") (pinfunction "2_2") (pintype "passive"))
    )
    (net (code "147") (name "unconnected-(J3-Pad3)") (class "Default")
      (node (ref "J3") (pin "3") (pinfunction "3_3") (pintype "passive"))
    )
    (net (code "148") (name "unconnected-(J3-Pad4)") (class "Default")
      (node (ref "J3") (pin "4") (pinfunction "4_4") (pintype "passive"))
    )
    (net (code "149") (name "unconnected-(J3-Pad5)") (class "Default")
      (node (ref "J3") (pin "5") (pinfunction "5_5") (pintype "passive"))
    )
    (net (code "150") (name "unconnected-(J3-Pad6)") (class "Default")
      (node (ref "J3") (pin "6") (pinfunction "6_6") (pintype "passive"))
    )
    (net (code "151") (name "unconnected-(J3-Pad7)") (class "Default")
      (node (ref "J3") (pin "7") (pinfunction "7_7") (pintype "passive"))
    )
    (net (code "152") (name "unconnected-(J3-Pad8)") (class "Default")
      (node (ref "J3") (pin "8") (pinfunction "8_8") (pintype "passive"))
    )
    (net (code "153") (name "unconnected-(J3-Pad9)") (class "Default")
      (node (ref "J3") (pin "9") (pinfunction "9_9") (pintype "passive"))
    )
    (net (code "154") (name "unconnected-(J3-Pad10)") (class "Default")
      (node (ref "J3") (pin "10") (pinfunction "10_10") (pintype "passive"))
    )
    (net (code "155") (name "unconnected-(J3-Pad11)") (class "Default")
      (node (ref "J3") (pin "11") (pinfunction "11_11") (pintype "passive"))
    )
    (net (code "156") (name "unconnected-(J3-Pad12)") (class "Default")
      (node (ref "J3") (pin "12") (pinfunction "12_12") (pintype "passive"))
    )
    (net (code "157") (name "unconnected-(J3-Pad13)") (class "Default")
      (node (ref "J3") (pin "13") (pinfunction "13_13") (pintype "passive"))
    )
    (net (code "158") (name "unconnected-(J3-Pad14)") (class "Default")
      (node (ref "J3") (pin "14") (pinfunction "14_14") (pintype "passive"))
    )
    (net (code "159") (name "unconnected-(J3-Pad15)") (class "Default")
      (node (ref "J3") (pin "15") (pinfunction "15_15") (pintype "passive"))
    )
    (net (code "160") (name "unconnected-(J3-Pad16)") (class "Default")
      (node (ref "J3") (pin "16") (pinfunction "16_16") (pintype "passive"))
    )
    (net (code "161") (name "unconnected-(J3-Pad17)") (class "Default")
      (node (ref "J3") (pin "17") (pinfunction "17_17") (pintype "passive"))
    )
    (net (code "162") (name "unconnected-(J3-Pad18)") (class "Default")
      (node (ref "J3") (pin "18") (pinfunction "18_18") (pintype "passive"))
    )
    (net (code "163") (name "unconnected-(J3-Pad19)") (class "Default")
      (node (ref "J3") (pin "19") (pinfunction "19_19") (pintype "passive"))
    )
    (net (code "164") (name "unconnected-(J3-Pad20)") (class "Default")
      (node (ref "J3") (pin "20") (pinfunction "20_20") (pintype "passive"))
    )
    (net (code "165") (name "unconnected-(J3-Pad21)") (class "Default")
      (node (ref "J3") (pin "21") (pinfunction "21_21") (pintype "passive"))
    )
    (net (code "166") (name "unconnected-(J3-Pad22)") (class "Default")
      (node (ref "J3") (pin "22") (pinfunction "22_22") (pintype "passive"))
    )
    (net (code "167") (name "unconnected-(J3-Pad23)") (class "Default")
      (node (ref "J3") (pin "23") (pinfunction "23_23") (pintype "passive"))
    )
    (net (code "168") (name "unconnected-(J3-Pad24)") (class "Default")
      (node (ref "J3") (pin "24") (pinfunction "24_24") (pintype "passive"))
    )
    (net (code "169") (name "unconnected-(J3-Pad25)") (class "Default")
      (node (ref "J3") (pin "25") (pinfunction "25_25") (pintype "passive"))
    )
    (net (code "170") (name "unconnected-(J3-Pad26)") (class "Default")
      (node (ref "J3") (pin "26") (pinfunction "26_26") (pintype "passive"))
    )
    (net (code "171") (name "unconnected-(J3-Pad27)") (class "Default")
      (node (ref "J3") (pin "27") (pinfunction "27_27") (pintype "passive"))
    )
    (net (code "172") (name "unconnected-(J3-Pad28)") (class "Default")
      (node (ref "J3") (pin "28") (pinfunction "28_28") (pintype "passive"))
    )
    (net (code "173") (name "unconnected-(J3-Pad29)") (class "Default")
      (node (ref "J3") (pin "29") (pinfunction "29_29") (pintype "passive"))
    )
    (net (code "174") (name "unconnected-(J3-Pad30)") (class "Default")
      (node (ref "J3") (pin "30") (pinfunction "30_30") (pintype "passive"))
    )
    (net (code "175") (name "unconnected-(J3-Pad31)") (class "Default")
      (node (ref "J3") (pin "31") (pinfunction "31_31") (pintype "passive"))
    )
    (net (code "176") (name "unconnected-(J3-Pad32)") (class "Default")
      (node (ref "J3") (pin "32") (pinfunction "32_32") (pintype "passive"))
    )
    (net (code "177") (name "unconnected-(J3-Pad33)") (class "Default")
      (node (ref "J3") (pin "33") (pinfunction "33_33") (pintype "passive"))
    )
    (net (code "178") (name "unconnected-(J3-Pad34)") (class "Default")
      (node (ref "J3") (pin "34") (pinfunction "34_34") (pintype "passive"))
    )
    (net (code "179") (name "unconnected-(J3-Pad35)") (class "Default")
      (node (ref "J3") (pin "35") (pinfunction "35_35") (pintype "passive"))
    )
    (net (code "180") (name "unconnected-(J3-Pad36)") (class "Default")
      (node (ref "J3") (pin "36") (pinfunction "36_36") (pintype "passive"))
    )
    (net (code "181") (name "unconnected-(J3-Pad37)") (class "Default")
      (node (ref "J3") (pin "37") (pinfunction "37_37") (pintype "passive"))
    )
    (net (code "182") (name "unconnected-(J3-Pad38)") (class "Default")
      (node (ref "J3") (pin "38") (pinfunction "38_38") (pintype "passive"))
    )
    (net (code "183") (name "unconnected-(J3-Pad39)") (class "Default")
      (node (ref "J3") (pin "39") (pinfunction "39_39") (pintype "passive"))
    )
    (net (code "184") (name "unconnected-(J3-Pad40)") (class "Default")
      (node (ref "J3") (pin "40") (pinfunction "40_40") (pintype "passive"))
    )
    (net (code "185") (name "unconnected-(J3-Pad41)") (class "Default")
      (node (ref "J3") (pin "41") (pinfunction "41_41") (pintype "passive"))
    )
    (net (code "186") (name "unconnected-(J3-Pad42)") (class "Default")
      (node (ref "J3") (pin "42") (pinfunction "42_42") (pintype "passive"))
    )
    (net (code "187") (name "unconnected-(J3-Pad43)") (class "Default")
      (node (ref "J3") (pin "43") (pinfunction "43_43") (pintype "passive"))
    )
    (net (code "188") (name "unconnected-(J3-Pad44)") (class "Default")
      (node (ref "J3") (pin "44") (pinfunction "44_44") (pintype "passive"))
    )
    (net (code "189") (name "unconnected-(J3-Pad45)") (class "Default")
      (node (ref "J3") (pin "45") (pinfunction "45_45") (pintype "passive"))
    )
    (net (code "190") (name "unconnected-(J3-Pad46)") (class "Default")
      (node (ref "J3") (pin "46") (pinfunction "46_46") (pintype "passive"))
    )
    (net (code "191") (name "unconnected-(J3-Pad47)") (class "Default")
      (node (ref "J3") (pin "47") (pinfunction "47_47") (pintype "passive"))
    )
    (net (code "192") (name "unconnected-(J3-Pad48)") (class "Default")
      (node (ref "J3") (pin "48") (pinfunction "48_48") (pintype "passive"))
    )
    (net (code "193") (name "unconnected-(J3-Pad49)") (class "Default")
      (node (ref "J3") (pin "49") (pinfunction "49_49") (pintype "passive"))
    )
    (net (code "194") (name "unconnected-(J3-Pad50)") (class "Default")
      (node (ref "J3") (pin "50") (pinfunction "50_50") (pintype "passive"))
    )
    (net (code "195") (name "unconnected-(J3-Pad51)") (class "Default")
      (node (ref "J3") (pin "51") (pinfunction "51_51") (pintype "passive"))
    )
    (net (code "196") (name "unconnected-(J3-Pad52)") (class "Default")
      (node (ref "J3") (pin "52") (pinfunction "52_52") (pintype "passive"))
    )
    (net (code "197") (name "unconnected-(J3-Pad53)") (class "Default")
      (node (ref "J3") (pin "53") (pinfunction "53_53") (pintype "passive"))
    )
    (net (code "198") (name "unconnected-(J3-Pad54)") (class "Default")
      (node (ref "J3") (pin "54") (pinfunction "54_54") (pintype "passive"))
    )
    (net (code "199") (name "unconnected-(J3-Pad55)") (class "Default")
      (node (ref "J3") (pin "55") (pinfunction "55_55") (pintype "passive"))
    )
    (net (code "200") (name "unconnected-(J3-Pad56)") (class "Default")
      (node (ref "J3") (pin "56") (pinfunction "56_56") (pintype "passive"))
    )
    (net (code "201") (name "unconnected-(J3-Pad57)") (class "Default")
      (node (ref "J3") (pin "57") (pinfunction "57_57") (pintype "passive"))
    )
    (net (code "202") (name "unconnected-(J3-Pad58)") (class "Default")
      (node (ref "J3") (pin "58") (pinfunction "58_58") (pintype "passive"))
    )
    (net (code "203") (name "unconnected-(J3-Pad59)") (class "Default")
      (node (ref "J3") (pin "59") (pinfunction "59_59") (pintype "passive"))
    )
    (net (code "204") (name "unconnected-(J3-Pad60)") (class "Default")
      (node (ref "J3") (pin "60") (pinfunction "60_60") (pintype "passive"))
    )
    (net (code "205") (name "unconnected-(J3-Pad61)") (class "Default")
      (node (ref "J3") (pin "61") (pinfunction "61_61") (pintype "passive"))
    )
    (net (code "206") (name "unconnected-(J3-Pad62)") (class "Default")
      (node (ref "J3") (pin "62") (pinfunction "62_62") (pintype "passive"))
    )
    (net (code "207") (name "unconnected-(J3-Pad63)") (class "Default")
      (node (ref "J3") (pin "63") (pinfunction "63_63") (pintype "passive"))
    )
    (net (code "208") (name "unconnected-(J3-Pad64)") (class "Default")
      (node (ref "J3") (pin "64") (pinfunction "64_64") (pintype "passive"))
    )
    (net (code "209") (name "unconnected-(J3-Pad65)") (class "Default")
      (node (ref "J3") (pin "65") (pinfunction "65_65") (pintype "passive"))
    )
    (net (code "210") (name "unconnected-(J3-Pad66)") (class "Default")
      (node (ref "J3") (pin "66") (pinfunction "66_66") (pintype "passive"))
    )
    (net (code "211") (name "unconnected-(J3-Pad67)") (class "Default")
      (node (ref "J3") (pin "67") (pinfunction "67_67") (pintype "passive"))
    )
    (net (code "212") (name "unconnected-(J3-Pad68)") (class "Default")
      (node (ref "J3") (pin "68") (pinfunction "68_68") (pintype "passive"))
    )
    (net (code "213") (name "unconnected-(J3-Pad69)") (class "Default")
      (node (ref "J3") (pin "69") (pinfunction "69_69") (pintype "passive"))
    )
    (net (code "214") (name "unconnected-(J3-Pad70)") (class "Default")
      (node (ref "J3") (pin "70") (pinfunction "70_70") (pintype "passive"))
    )
    (net (code "215") (name "unconnected-(J3-Pad71)") (class "Default")
      (node (ref "J3") (pin "71") (pinfunction "71_71") (pintype "passive"))
    )
    (net (code "216") (name "unconnected-(J3-Pad72)") (class "Default")
      (node (ref "J3") (pin "72") (pinfunction "72_72") (pintype "passive"))
    )
    (net (code "217") (name "unconnected-(J3-Pad73)") (class "Default")
      (node (ref "J3") (pin "73") (pinfunction "73_73") (pintype "passive"))
    )
    (net (code "218") (name "unconnected-(J3-Pad74)") (class "Default")
      (node (ref "J3") (pin "74") (pinfunction "74_74") (pintype "passive"))
    )
    (net (code "219") (name "unconnected-(J3-Pad75)") (class "Default")
      (node (ref "J3") (pin "75") (pinfunction "75_75") (pintype "passive"))
    )
    (net (code "220") (name "unconnected-(J3-Pad76)") (class "Default")
      (node (ref "J3") (pin "76") (pinfunction "76_76") (pintype "passive"))
    )
    (net (code "221") (name "unconnected-(J3-Pad77)") (class "Default")
      (node (ref "J3") (pin "77") (pinfunction "77_77") (pintype "passive"))
    )
    (net (code "222") (name "unconnected-(J3-Pad78)") (class "Default")
      (node (ref "J3") (pin "78") (pinfunction "78_78") (pintype "passive"))
    )
    (net (code "223") (name "unconnected-(J3-Pad79)") (class "Default")
      (node (ref "J3") (pin "79") (pinfunction "79_79") (pintype "passive"))
    )
    (net (code "224") (name "unconnected-(J3-Pad80)") (class "Default")
      (node (ref "J3") (pin "80") (pinfunction "80_80") (pintype "passive"))
    )
    (net (code "225") (name "unconnected-(J3-Pad81)") (class "Default")
      (node (ref "J3") (pin "81") (pinfunction "81_81") (pintype "passive"))
    )
    (net (code "226") (name "unconnected-(J3-Pad82)") (class "Default")
      (node (ref "J3") (pin "82") (pinfunction "82_82") (pintype "passive"))
    )
    (net (code "227") (name "unconnected-(J3-Pad83)") (class "Default")
      (node (ref "J3") (pin "83") (pinfunction "83_83") (pintype "passive"))
    )
    (net (code "228") (name "unconnected-(J3-Pad84)") (class "Default")
      (node (ref "J3") (pin "84") (pinfunction "84_84") (pintype "passive"))
    )
    (net (code "229") (name "unconnected-(J3-Pad85)") (class "Default")
      (node (ref "J3") (pin "85") (pinfunction "85_85") (pintype "passive"))
    )
    (net (code "230") (name "unconnected-(J3-Pad86)") (class "Default")
      (node (ref "J3") (pin "86") (pinfunction "86_86") (pintype "passive"))
    )
    (net (code "231") (name "unconnected-(J3-Pad87)") (class "Default")
      (node (ref "J3") (pin "87") (pinfunction "87_87") (pintype "passive"))
    )
    (net (code "232") (name "unconnected-(J3-Pad88)") (class "Default")
      (node (ref "J3") (pin "88") (pinfunction "88_88") (pintype "passive"))
    )
    (net (code "233") (name "unconnected-(J3-Pad89)") (class "Default")
      (node (ref "J3") (pin "89") (pinfunction "89_89") (pintype "passive"))
    )
    (net (code "234") (name "unconnected-(J3-Pad90)") (class "Default")
      (node (ref "J3") (pin "90") (pinfunction "90_90") (pintype "passive"))
    )
    (net (code "235") (name "unconnected-(J3-Pad91)") (class "Default")
      (node (ref "J3") (pin "91") (pinfunction "91_91") (pintype "passive"))
    )
    (net (code "236") (name "unconnected-(J3-Pad92)") (class "Default")
      (node (ref "J3") (pin "92") (pinfunction "92_92") (pintype "passive"))
    )
    (net (code "237") (name "unconnected-(J3-Pad93)") (class "Default")
      (node (ref "J3") (pin "93") (pinfunction "93_93") (pintype "passive"))
    )
    (net (code "238") (name "unconnected-(J3-Pad94)") (class "Default")
      (node (ref "J3") (pin "94") (pinfunction "94_94") (pintype "passive"))
    )
    (net (code "239") (name "unconnected-(J3-Pad95)") (class "Default")
      (node (ref "J3") (pin "95") (pinfunction "95_95") (pintype "passive"))
    )
    (net (code "240") (name "unconnected-(J3-Pad96)") (class "Default")
      (node (ref "J3") (pin "96") (pinfunction "96_96") (pintype "passive"))
    )
    (net (code "241") (name "unconnected-(J3-Pad97)") (class "Default")
      (node (ref "J3") (pin "97") (pinfunction "97_97") (pintype "passive"))
    )
    (net (code "242") (name "unconnected-(J3-Pad98)") (class "Default")
      (node (ref "J3") (pin "98") (pinfunction "98_98") (pintype "passive"))
    )
    (net (code "243") (name "unconnected-(J3-Pad99)") (class "Default")
      (node (ref "J3") (pin "99") (pinfunction "99_99") (pintype "passive"))
    )
    (net (code "244") (name "unconnected-(J3-Pad100)") (class "Default")
      (node (ref "J3") (pin "100") (pinfunction "100_100") (pintype "passive"))
    )
    (net (code "245") (name "unconnected-(J6-Pad1)") (class "Default")
      (node (ref "J6") (pin "1") (pinfunction "1_1") (pintype "passive"))
    )
    (net (code "246") (name "unconnected-(J6-Pad2)") (class "Default")
      (node (ref "J6") (pin "2") (pinfunction "2_2") (pintype "passive"))
    )
    (net (code "247") (name "unconnected-(J6-Pad3)") (class "Default")
      (node (ref "J6") (pin "3") (pinfunction "3_3") (pintype "passive"))
    )
    (net (code "248") (name "unconnected-(J6-Pad4)") (class "Default")
      (node (ref "J6") (pin "4") (pinfunction "4_4") (pintype "passive"))
    )
    (net (code "249") (name "unconnected-(J6-Pad5)") (class "Default")
      (node (ref "J6") (pin "5") (pinfunction "5_5") (pintype "passive"))
    )
    (net (code "250") (name "unconnected-(J6-Pad6)") (class "Default")
      (node (ref "J6") (pin "6") (pinfunction "6_6") (pintype "passive"))
    )
    (net (code "251") (name "unconnected-(J6-Pad7)") (class "Default")
      (node (ref "J6") (pin "7") (pinfunction "7_7") (pintype "passive"))
    )
    (net (code "252") (name "unconnected-(J6-Pad8)") (class "Default")
      (node (ref "J6") (pin "8") (pinfunction "8_8") (pintype "passive"))
    )
    (net (code "253") (name "unconnected-(J6-Pad9)") (class "Default")
      (node (ref "J6") (pin "9") (pinfunction "9_9") (pintype "passive"))
    )
    (net (code "254") (name "unconnected-(J6-Pad10)") (class "Default")
      (node (ref "J6") (pin "10") (pinfunction "10_10") (pintype "passive"))
    )
    (net (code "255") (name "unconnected-(J6-Pad11)") (class "Default")
      (node (ref "J6") (pin "11") (pinfunction "11_11") (pintype "passive"))
    )
    (net (code "256") (name "unconnected-(J6-Pad12)") (class "Default")
      (node (ref "J6") (pin "12") (pinfunction "12_12") (pintype "passive"))
    )
    (net (code "257") (name "unconnected-(J6-Pad13)") (class "Default")
      (node (ref "J6") (pin "13") (pinfunction "13_13") (pintype "passive"))
    )
    (net (code "258") (name "unconnected-(J6-Pad14)") (class "Default")
      (node (ref "J6") (pin "14") (pinfunction "14_14") (pintype "passive"))
    )
    (net (code "259") (name "unconnected-(J6-Pad15)") (class "Default")
      (node (ref "J6") (pin "15") (pinfunction "15_15") (pintype "passive"))
    )
    (net (code "260") (name "unconnected-(J6-Pad16)") (class "Default")
      (node (ref "J6") (pin "16") (pinfunction "16_16") (pintype "passive"))
    )
    (net (code "261") (name "unconnected-(J6-Pad17)") (class "Default")
      (node (ref "J6") (pin "17") (pinfunction "17_17") (pintype "passive"))
    )
    (net (code "262") (name "unconnected-(J6-Pad18)") (class "Default")
      (node (ref "J6") (pin "18") (pinfunction "18_18") (pintype "passive"))
    )
    (net (code "263") (name "unconnected-(J6-Pad19)") (class "Default")
      (node (ref "J6") (pin "19") (pinfunction "19_19") (pintype "passive"))
    )
    (net (code "264") (name "unconnected-(J6-Pad20)") (class "Default")
      (node (ref "J6") (pin "20") (pinfunction "20_20") (pintype "passive"))
    )
    (net (code "265") (name "unconnected-(J6-Pad21)") (class "Default")
      (node (ref "J6") (pin "21") (pinfunction "21_21") (pintype "passive"))
    )
    (net (code "266") (name "unconnected-(J6-Pad22)") (class "Default")
      (node (ref "J6") (pin "22") (pinfunction "22_22") (pintype "passive"))
    )
    (net (code "267") (name "unconnected-(J6-Pad23)") (class "Default")
      (node (ref "J6") (pin "23") (pinfunction "23_23") (pintype "passive"))
    )
    (net (code "268") (name "unconnected-(J6-Pad24)") (class "Default")
      (node (ref "J6") (pin "24") (pinfunction "24_24") (pintype "passive"))
    )
    (net (code "269") (name "unconnected-(J6-Pad25)") (class "Default")
      (node (ref "J6") (pin "25") (pinfunction "25_25") (pintype "passive"))
    )
    (net (code "270") (name "unconnected-(J6-Pad26)") (class "Default")
      (node (ref "J6") (pin "26") (pinfunction "26_26") (pintype "passive"))
    )
    (net (code "271") (name "unconnected-(J6-Pad27)") (class "Default")
      (node (ref "J6") (pin "27") (pinfunction "27_27") (pintype "passive"))
    )
    (net (code "272") (name "unconnected-(J6-Pad28)") (class "Default")
      (node (ref "J6") (pin "28") (pinfunction "28_28") (pintype "passive"))
    )
    (net (code "273") (name "unconnected-(J6-Pad29)") (class "Default")
      (node (ref "J6") (pin "29") (pinfunction "29_29") (pintype "passive"))
    )
    (net (code "274") (name "unconnected-(J6-Pad30)") (class "Default")
      (node (ref "J6") (pin "30") (pinfunction "30_30") (pintype "passive"))
    )
    (net (code "275") (name "unconnected-(J6-Pad31)") (class "Default")
      (node (ref "J6") (pin "31") (pinfunction "31_31") (pintype "passive"))
    )
    (net (code "276") (name "unconnected-(J6-Pad32)") (class "Default")
      (node (ref "J6") (pin "32") (pinfunction "32_32") (pintype "passive"))
    )
    (net (code "277") (name "unconnected-(J6-Pad33)") (class "Default")
      (node (ref "J6") (pin "33") (pinfunction "33_33") (pintype "passive"))
    )
    (net (code "278") (name "unconnected-(J6-Pad34)") (class "Default")
      (node (ref "J6") (pin "34") (pinfunction "34_34") (pintype "passive"))
    )
    (net (code "279") (name "unconnected-(J6-Pad35)") (class "Default")
      (node (ref "J6") (pin "35") (pinfunction "35_35") (pintype "passive"))
    )
    (net (code "280") (name "unconnected-(J6-Pad36)") (class "Default")
      (node (ref "J6") (pin "36") (pinfunction "36_36") (pintype "passive"))
    )
    (net (code "281") (name "unconnected-(J6-Pad37)") (class "Default")
      (node (ref "J6") (pin "37") (pinfunction "37_37") (pintype "passive"))
    )
    (net (code "282") (name "unconnected-(J6-Pad38)") (class "Default")
      (node (ref "J6") (pin "38") (pinfunction "38_38") (pintype "passive"))
    )
    (net (code "283") (name "unconnected-(J6-Pad39)") (class "Default")
      (node (ref "J6") (pin "39") (pinfunction "39_39") (pintype "passive"))
    )
    (net (code "284") (name "unconnected-(J6-Pad40)") (class "Default")
      (node (ref "J6") (pin "40") (pinfunction "40_40") (pintype "passive"))
    )
    (net (code "285") (name "unconnected-(J6-Pad41)") (class "Default")
      (node (ref "J6") (pin "41") (pinfunction "41_41") (pintype "passive"))
    )
    (net (code "286") (name "unconnected-(J6-Pad42)") (class "Default")
      (node (ref "J6") (pin "42") (pinfunction "42_42") (pintype "passive"))
    )
    (net (code "287") (name "unconnected-(J6-Pad43)") (class "Default")
      (node (ref "J6") (pin "43") (pinfunction "43_43") (pintype "passive"))
    )
    (net (code "288") (name "unconnected-(J6-Pad44)") (class "Default")
      (node (ref "J6") (pin "44") (pinfunction "44_44") (pintype "passive"))
    )
    (net (code "289") (name "unconnected-(J6-Pad45)") (class "Default")
      (node (ref "J6") (pin "45") (pinfunction "45_45") (pintype "passive"))
    )
    (net (code "290") (name "unconnected-(J6-Pad46)") (class "Default")
      (node (ref "J6") (pin "46") (pinfunction "46_46") (pintype "passive"))
    )
    (net (code "291") (name "unconnected-(J6-Pad47)") (class "Default")
      (node (ref "J6") (pin "47") (pinfunction "47_47") (pintype "passive"))
    )
    (net (code "292") (name "unconnected-(J6-Pad48)") (class "Default")
      (node (ref "J6") (pin "48") (pinfunction "48_48") (pintype "passive"))
    )
    (net (code "293") (name "unconnected-(J6-Pad49)") (class "Default")
      (node (ref "J6") (pin "49") (pinfunction "49_49") (pintype "passive"))
    )
    (net (code "294") (name "unconnected-(J6-Pad50)") (class "Default")
      (node (ref "J6") (pin "50") (pinfunction "50_50") (pintype "passive"))
    )
    (net (code "295") (name "unconnected-(J6-Pad51)") (class "Default")
      (node (ref "J6") (pin "51") (pinfunction "51_51") (pintype "passive"))
    )
    (net (code "296") (name "unconnected-(J6-Pad52)") (class "Default")
      (node (ref "J6") (pin "52") (pinfunction "52_52") (pintype "passive"))
    )
    (net (code "297") (name "unconnected-(J6-Pad53)") (class "Default")
      (node (ref "J6") (pin "53") (pinfunction "53_53") (pintype "passive"))
    )
    (net (code "298") (name "unconnected-(J6-Pad54)") (class "Default")
      (node (ref "J6") (pin "54") (pinfunction "54_54") (pintype "passive"))
    )
    (net (code "299") (name "unconnected-(J6-Pad55)") (class "Default")
      (node (ref "J6") (pin "55") (pinfunction "55_55") (pintype "passive"))
    )
    (net (code "300") (name "unconnected-(J6-Pad56)") (class "Default")
      (node (ref "J6") (pin "56") (pinfunction "56_56") (pintype "passive"))
    )
    (net (code "301") (name "unconnected-(J6-Pad57)") (class "Default")
      (node (ref "J6") (pin "57") (pinfunction "57_57") (pintype "passive"))
    )
    (net (code "302") (name "unconnected-(J6-Pad58)") (class "Default")
      (node (ref "J6") (pin "58") (pinfunction "58_58") (pintype "passive"))
    )
    (net (code "303") (name "unconnected-(J6-Pad59)") (class "Default")
      (node (ref "J6") (pin "59") (pinfunction "59_59") (pintype "passive"))
    )
    (net (code "304") (name "unconnected-(J6-Pad60)") (class "Default")
      (node (ref "J6") (pin "60") (pinfunction "60_60") (pintype "passive"))
    )
    (net (code "305") (name "unconnected-(J6-Pad61)") (class "Default")
      (node (ref "J6") (pin "61") (pinfunction "61_61") (pintype "passive"))
    )
    (net (code "306") (name "unconnected-(J6-Pad62)") (class "Default")
      (node (ref "J6") (pin "62") (pinfunction "62_62") (pintype "passive"))
    )
    (net (code "307") (name "unconnected-(J6-Pad63)") (class "Default")
      (node (ref "J6") (pin "63") (pinfunction "63_63") (pintype "passive"))
    )
    (net (code "308") (name "unconnected-(J6-Pad64)") (class "Default")
      (node (ref "J6") (pin "64") (pinfunction "64_64") (pintype "passive"))
    )
    (net (code "309") (name "unconnected-(J6-Pad65)") (class "Default")
      (node (ref "J6") (pin "65") (pinfunction "65_65") (pintype "passive"))
    )
    (net (code "310") (name "unconnected-(J6-Pad66)") (class "Default")
      (node (ref "J6") (pin "66") (pinfunction "66_66") (pintype "passive"))
    )
    (net (code "311") (name "unconnected-(J6-Pad67)") (class "Default")
      (node (ref "J6") (pin "67") (pinfunction "67_67") (pintype "passive"))
    )
    (net (code "312") (name "unconnected-(J6-Pad68)") (class "Default")
      (node (ref "J6") (pin "68") (pinfunction "68_68") (pintype "passive"))
    )
    (net (code "313") (name "unconnected-(J6-Pad69)") (class "Default")
      (node (ref "J6") (pin "69") (pinfunction "69_69") (pintype "passive"))
    )
    (net (code "314") (name "unconnected-(J6-Pad70)") (class "Default")
      (node (ref "J6") (pin "70") (pinfunction "70_70") (pintype "passive"))
    )
    (net (code "315") (name "unconnected-(J6-Pad71)") (class "Default")
      (node (ref "J6") (pin "71") (pinfunction "71_71") (pintype "passive"))
    )
    (net (code "316") (name "unconnected-(J6-Pad72)") (class "Default")
      (node (ref "J6") (pin "72") (pinfunction "72_72") (pintype "passive"))
    )
    (net (code "317") (name "unconnected-(J6-Pad73)") (class "Default")
      (node (ref "J6") (pin "73") (pinfunction "73_73") (pintype "passive"))
    )
    (net (code "318") (name "unconnected-(J6-Pad74)") (class "Default")
      (node (ref "J6") (pin "74") (pinfunction "74_74") (pintype "passive"))
    )
    (net (code "319") (name "unconnected-(J6-Pad75)") (class "Default")
      (node (ref "J6") (pin "75") (pinfunction "75_75") (pintype "passive"))
    )
    (net (code "320") (name "unconnected-(J6-Pad76)") (class "Default")
      (node (ref "J6") (pin "76") (pinfunction "76_76") (pintype "passive"))
    )
    (net (code "321") (name "unconnected-(J6-Pad77)") (class "Default")
      (node (ref "J6") (pin "77") (pinfunction "77_77") (pintype "passive"))
    )
    (net (code "322") (name "unconnected-(J6-Pad78)") (class "Default")
      (node (ref "J6") (pin "78") (pinfunction "78_78") (pintype "passive"))
    )
    (net (code "323") (name "unconnected-(J6-Pad79)") (class "Default")
      (node (ref "J6") (pin "79") (pinfunction "79_79") (pintype "passive"))
    )
    (net (code "324") (name "unconnected-(J6-Pad80)") (class "Default")
      (node (ref "J6") (pin "80") (pinfunction "80_80") (pintype "passive"))
    )
    (net (code "325") (name "unconnected-(J6-Pad81)") (class "Default")
      (node (ref "J6") (pin "81") (pinfunction "81_81") (pintype "passive"))
    )
    (net (code "326") (name "unconnected-(J6-Pad82)") (class "Default")
      (node (ref "J6") (pin "82") (pinfunction "82_82") (pintype "passive"))
    )
    (net (code "327") (name "unconnected-(J6-Pad83)") (class "Default")
      (node (ref "J6") (pin "83") (pinfunction "83_83") (pintype "passive"))
    )
    (net (code "328") (name "unconnected-(J6-Pad84)") (class "Default")
      (node (ref "J6") (pin "84") (pinfunction "84_84") (pintype "passive"))
    )
    (net (code "329") (name "unconnected-(J6-Pad85)") (class "Default")
      (node (ref "J6") (pin "85") (pinfunction "85_85") (pintype "passive"))
    )
    (net (code "330") (name "unconnected-(J6-Pad86)") (class "Default")
      (node (ref "J6") (pin "86") (pinfunction "86_86") (pintype "passive"))
    )
    (net (code "331") (name "unconnected-(J6-Pad87)") (class "Default")
      (node (ref "J6") (pin "87") (pinfunction "87_87") (pintype "passive"))
    )
    (net (code "332") (name "unconnected-(J6-Pad88)") (class "Default")
      (node (ref "J6") (pin "88") (pinfunction "88_88") (pintype "passive"))
    )
    (net (code "333") (name "unconnected-(J6-Pad89)") (class "Default")
      (node (ref "J6") (pin "89") (pinfunction "89_89") (pintype "passive"))
    )
    (net (code "334") (name "unconnected-(J6-Pad90)") (class "Default")
      (node (ref "J6") (pin "90") (pinfunction "90_90") (pintype "passive"))
    )
    (net (code "335") (name "unconnected-(J6-Pad91)") (class "Default")
      (node (ref "J6") (pin "91") (pinfunction "91_91") (pintype "passive"))
    )
    (net (code "336") (name "unconnected-(J6-Pad92)") (class "Default")
      (node (ref "J6") (pin "92") (pinfunction "92_92") (pintype "passive"))
    )
    (net (code "337") (name "unconnected-(J6-Pad93)") (class "Default")
      (node (ref "J6") (pin "93") (pinfunction "93_93") (pintype "passive"))
    )
    (net (code "338") (name "unconnected-(J6-Pad94)") (class "Default")
      (node (ref "J6") (pin "94") (pinfunction "94_94") (pintype "passive"))
    )
    (net (code "339") (name "unconnected-(J6-Pad95)") (class "Default")
      (node (ref "J6") (pin "95") (pinfunction "95_95") (pintype "passive"))
    )
    (net (code "340") (name "unconnected-(J6-Pad96)") (class "Default")
      (node (ref "J6") (pin "96") (pinfunction "96_96") (pintype "passive"))
    )
    (net (code "341") (name "unconnected-(J6-Pad97)") (class "Default")
      (node (ref "J6") (pin "97") (pinfunction "97_97") (pintype "passive"))
    )
    (net (code "342") (name "unconnected-(J6-Pad98)") (class "Default")
      (node (ref "J6") (pin "98") (pinfunction "98_98") (pintype "passive"))
    )
    (net (code "343") (name "unconnected-(J6-Pad99)") (class "Default")
      (node (ref "J6") (pin "99") (pinfunction "99_99") (pintype "passive"))
    )
    (net (code "344") (name "unconnected-(J6-Pad100)") (class "Default")
      (node (ref "J6") (pin "100") (pinfunction "100_100") (pintype "passive"))
    )
  )
)
